# Relay_Mux_Sheet1.net
KiCad netlist of a schematic drawn in Altium Designer
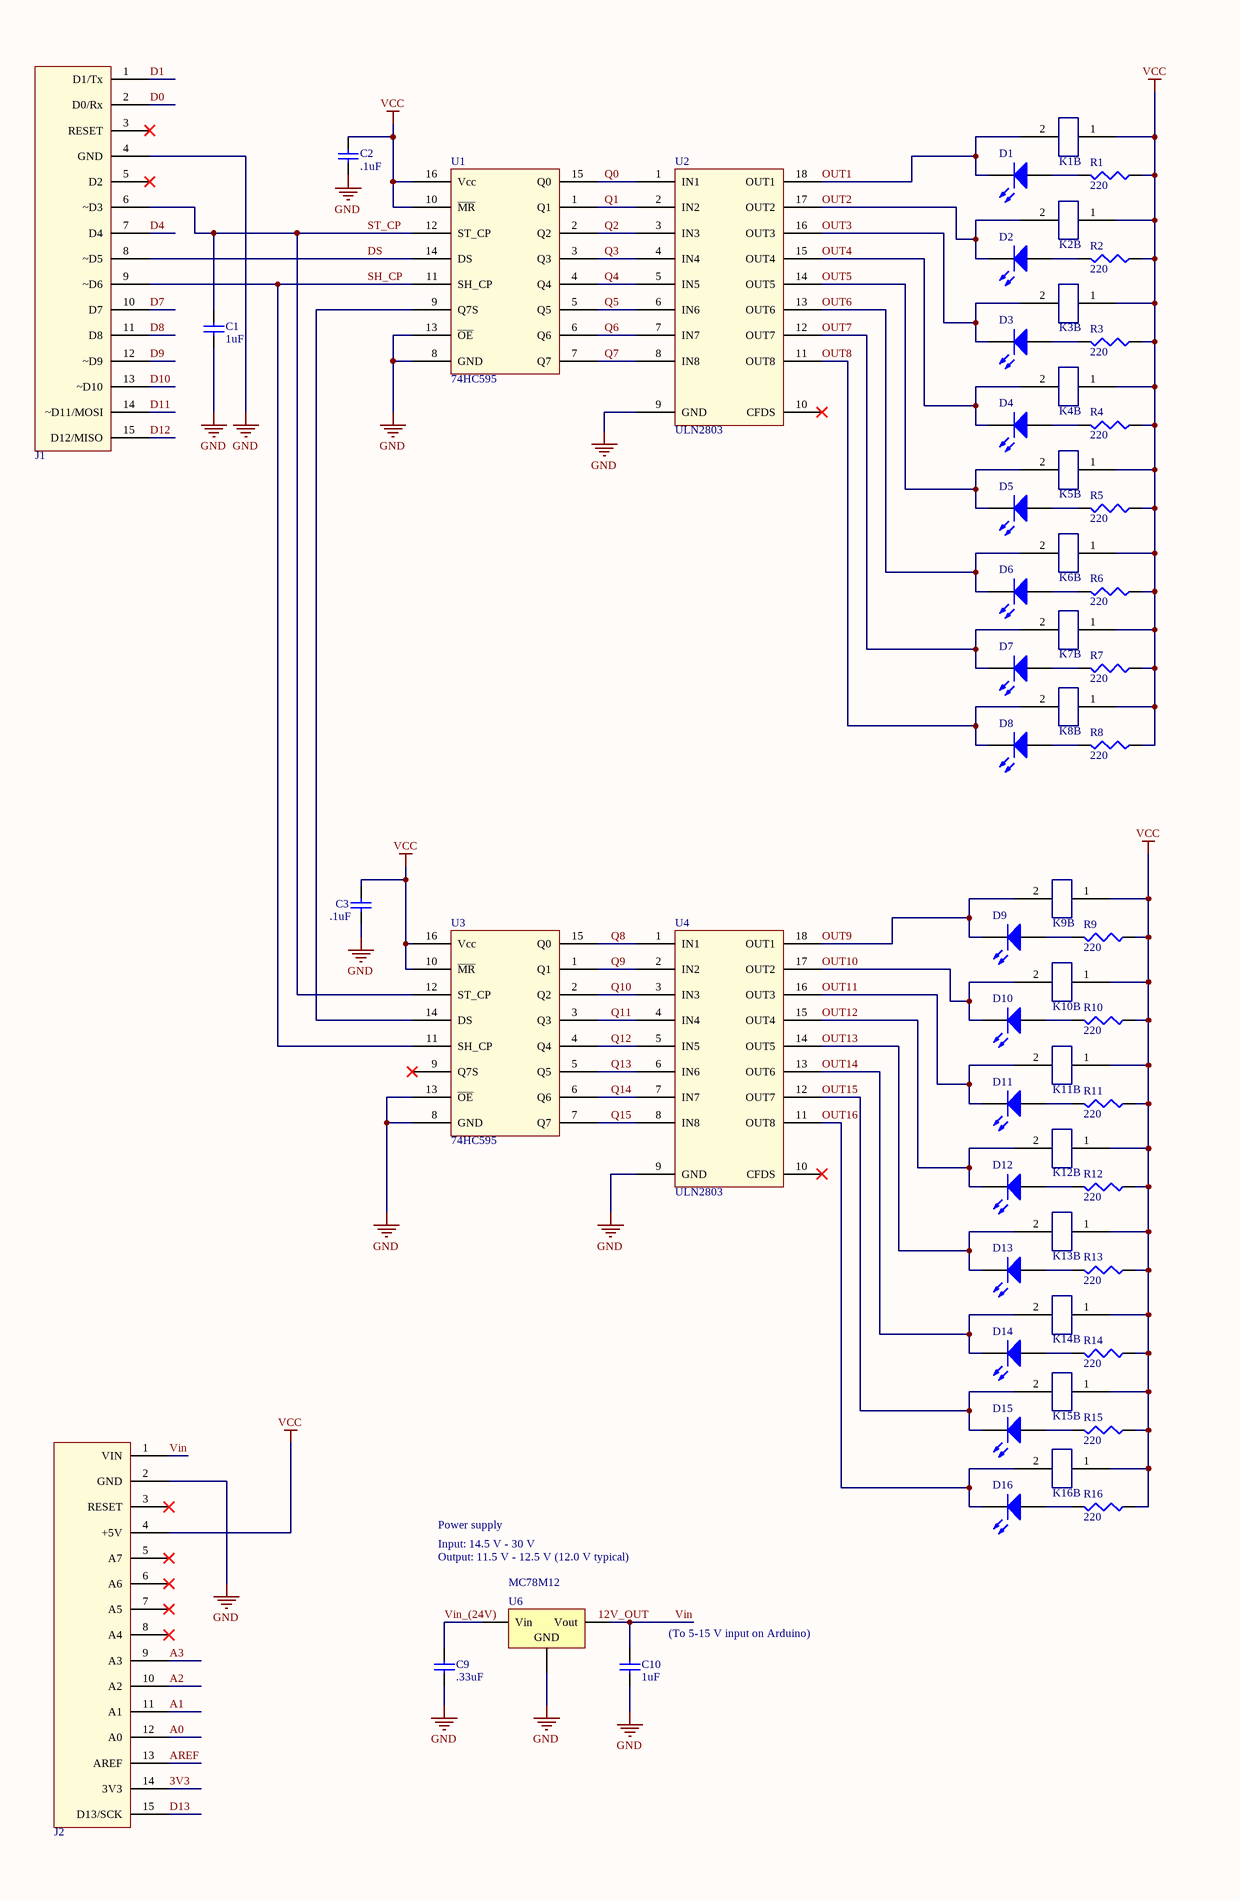
[diagram p0: Relay_Mux_Sheet1.SchDoc, left]
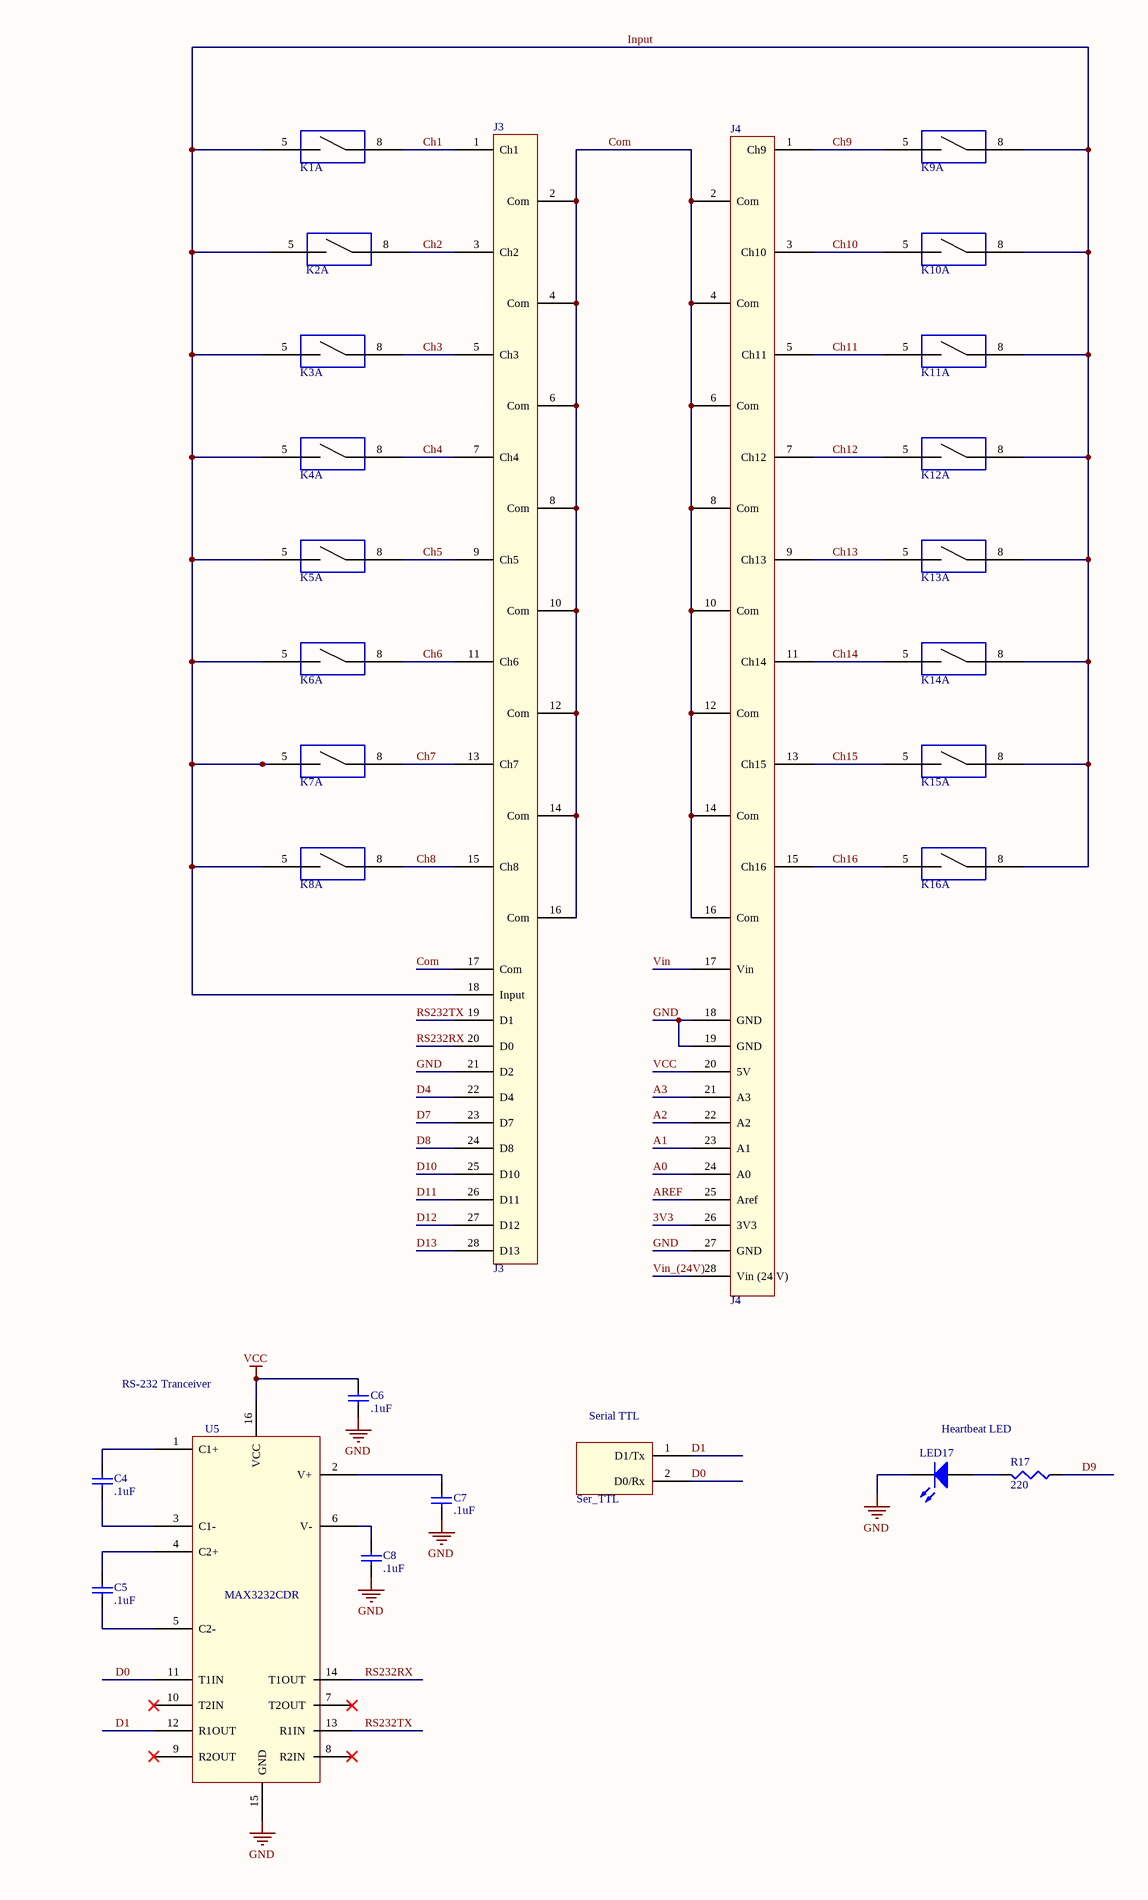
[diagram p1: Relay_Mux_Sheet1.SchDoc, right]

(export (version "E")
  (design (tool "Eeschema 10.0.6"))
  (components
    (comp (ref "C1")
      (value "1uF")
      (footprint "0603_Capacitor")
      (description "Capacitor")
      (fields (field (name "Comment") "Cap") (field (name "PUBLISHER") "Altium Limited"))
      (libsource (lib "Miscellaneous Devices") (part "Cap"))
    )
    (comp (ref "C2")
      (value ".1uF")
      (footprint "0603_Capacitor")
      (description "Capacitor")
      (fields (field (name "Comment") "Cap") (field (name "PUBLISHER") "Altium Limited"))
      (libsource (lib "Miscellaneous Devices") (part "Cap"))
    )
    (comp (ref "C3")
      (value ".1uF")
      (footprint "0603_Capacitor")
      (description "Capacitor")
      (fields (field (name "Comment") "Cap") (field (name "PUBLISHER") "Altium Limited"))
      (libsource (lib "Miscellaneous Devices") (part "Cap"))
    )
    (comp (ref "C4")
      (value ".1uF")
      (footprint "0603_Capacitor")
      (description "Capacitor")
      (fields (field (name "Comment") "Cap") (field (name "PUBLISHER") "Altium Limited"))
      (libsource (lib "Miscellaneous Devices") (part "Cap"))
    )
    (comp (ref "C5")
      (value ".1uF")
      (footprint "0603_Capacitor")
      (description "Capacitor")
      (fields (field (name "Comment") "Cap") (field (name "PUBLISHER") "Altium Limited"))
      (libsource (lib "Miscellaneous Devices") (part "Cap"))
    )
    (comp (ref "C6")
      (value ".1uF")
      (footprint "0603_Capacitor")
      (description "Capacitor")
      (fields (field (name "Comment") "Cap") (field (name "PUBLISHER") "Altium Limited"))
      (libsource (lib "Miscellaneous Devices") (part "Cap"))
    )
    (comp (ref "C7")
      (value ".1uF")
      (footprint "0603_Capacitor")
      (description "Capacitor")
      (fields (field (name "Comment") "Cap") (field (name "PUBLISHER") "Altium Limited"))
      (libsource (lib "Miscellaneous Devices") (part "Cap"))
    )
    (comp (ref "C8")
      (value ".1uF")
      (footprint "0603_Capacitor")
      (description "Capacitor")
      (fields (field (name "Comment") "Cap") (field (name "PUBLISHER") "Altium Limited"))
      (libsource (lib "Miscellaneous Devices") (part "Cap"))
    )
    (comp (ref "C9")
      (value ".33uF")
      (footprint "0603_Capacitor")
      (description "Capacitor")
      (fields (field (name "Comment") "Cap") (field (name "PUBLISHER") "Altium Limited"))
      (libsource (lib "Miscellaneous Devices") (part "Cap"))
    )
    (comp (ref "C10")
      (value "1uF")
      (footprint "0805_cap_CAPC3013X10N")
      (description "Capacitor")
      (fields (field (name "Comment") "Cap") (field (name "PUBLISHER") "Altium Limited"))
      (libsource (lib "Miscellaneous Devices") (part "Cap"))
    )
    (comp (ref "D1")
      (value "LED3")
      (footprint "LITE_ON_LED")
      (description "Typical BLUE SiC LED")
      (fields (field (name "PUBLISHER") "Altium Limited"))
      (libsource (lib "Miscellaneous Devices") (part "LED3"))
    )
    (comp (ref "D2")
      (value "LED3")
      (footprint "LITE_ON_LED")
      (description "Typical BLUE SiC LED")
      (fields (field (name "PUBLISHER") "Altium Limited"))
      (libsource (lib "Miscellaneous Devices") (part "LED3"))
    )
    (comp (ref "D3")
      (value "LED3")
      (footprint "LITE_ON_LED")
      (description "Typical BLUE SiC LED")
      (fields (field (name "PUBLISHER") "Altium Limited"))
      (libsource (lib "Miscellaneous Devices") (part "LED3"))
    )
    (comp (ref "D4")
      (value "LED3")
      (footprint "LITE_ON_LED")
      (description "Typical BLUE SiC LED")
      (fields (field (name "PUBLISHER") "Altium Limited"))
      (libsource (lib "Miscellaneous Devices") (part "LED3"))
    )
    (comp (ref "D5")
      (value "LED3")
      (footprint "LITE_ON_LED")
      (description "Typical BLUE SiC LED")
      (fields (field (name "PUBLISHER") "Altium Limited"))
      (libsource (lib "Miscellaneous Devices") (part "LED3"))
    )
    (comp (ref "D6")
      (value "LED3")
      (footprint "LITE_ON_LED")
      (description "Typical BLUE SiC LED")
      (fields (field (name "PUBLISHER") "Altium Limited"))
      (libsource (lib "Miscellaneous Devices") (part "LED3"))
    )
    (comp (ref "D7")
      (value "LED3")
      (footprint "LITE_ON_LED")
      (description "Typical BLUE SiC LED")
      (fields (field (name "PUBLISHER") "Altium Limited"))
      (libsource (lib "Miscellaneous Devices") (part "LED3"))
    )
    (comp (ref "D8")
      (value "LED3")
      (footprint "LITE_ON_LED")
      (description "Typical BLUE SiC LED")
      (fields (field (name "PUBLISHER") "Altium Limited"))
      (libsource (lib "Miscellaneous Devices") (part "LED3"))
    )
    (comp (ref "D9")
      (value "LED3")
      (footprint "LITE_ON_LED")
      (description "Typical BLUE SiC LED")
      (fields (field (name "PUBLISHER") "Altium Limited"))
      (libsource (lib "Miscellaneous Devices") (part "LED3"))
    )
    (comp (ref "D10")
      (value "LED3")
      (footprint "LITE_ON_LED")
      (description "Typical BLUE SiC LED")
      (fields (field (name "PUBLISHER") "Altium Limited"))
      (libsource (lib "Miscellaneous Devices") (part "LED3"))
    )
    (comp (ref "D11")
      (value "LED11")
      (footprint "LITE_ON_LED")
      (description "Typical BLUE SiC LED")
      (fields (field (name "PUBLISHER") "Altium Limited"))
      (libsource (lib "Miscellaneous Devices") (part "LED3"))
    )
    (comp (ref "D12")
      (value "LED3")
      (footprint "LITE_ON_LED")
      (description "Typical BLUE SiC LED")
      (fields (field (name "PUBLISHER") "Altium Limited"))
      (libsource (lib "Miscellaneous Devices") (part "LED3"))
    )
    (comp (ref "D13")
      (value "LED3")
      (footprint "LITE_ON_LED")
      (description "Typical BLUE SiC LED")
      (fields (field (name "PUBLISHER") "Altium Limited"))
      (libsource (lib "Miscellaneous Devices") (part "LED3"))
    )
    (comp (ref "D14")
      (value "LED3")
      (footprint "LITE_ON_LED")
      (description "Typical BLUE SiC LED")
      (fields (field (name "PUBLISHER") "Altium Limited"))
      (libsource (lib "Miscellaneous Devices") (part "LED3"))
    )
    (comp (ref "D15")
      (value "LED3")
      (footprint "LITE_ON_LED")
      (description "Typical BLUE SiC LED")
      (fields (field (name "PUBLISHER") "Altium Limited"))
      (libsource (lib "Miscellaneous Devices") (part "LED3"))
    )
    (comp (ref "D16")
      (value "LED3")
      (footprint "LITE_ON_LED")
      (description "Typical BLUE SiC LED")
      (fields (field (name "PUBLISHER") "Altium Limited"))
      (libsource (lib "Miscellaneous Devices") (part "LED3"))
    )
    (comp (ref "J1")
      (value "J1_Nano")
      (footprint "J1, J2 - Arduino Nano")
      (description "J1 on Arduino Nano")
      (libsource (lib "Relay_Mux") (part "J1"))
    )
    (comp (ref "J2")
      (value "J2_Nano")
      (footprint "J1, J2 - Arduino Nano")
      (description "J2 on Arduino Nano")
      (libsource (lib "Relay_Mux") (part "J2"))
    )
    (comp (ref "J3")
      (value "J3")
      (footprint "Term_Block_Amphenol_20020327")
      (libsource (lib "Relay_Mux") (part "J3"))
    )
    (comp (ref "J4")
      (value "J4")
      (footprint "Term_Block_Amphenol_20020327")
      (libsource (lib "Relay_Mux") (part "J4"))
    )
    (comp (ref "K1")
      (value "K*")
      (footprint "Relay_G6DN-1A DC5")
      (description "Relay, SPST, 5V")
      (libsource (lib "") (part "Relay_G6DN-1A DC5_1"))
    )
    (comp (ref "K2")
      (value "K*")
      (footprint "Relay_G6DN-1A DC5")
      (description "Relay, SPST, 5V")
      (libsource (lib "Relay_Mux") (part "Relay_G6DN-1A DC5"))
    )
    (comp (ref "K3")
      (value "K*")
      (footprint "Relay_G6DN-1A DC5")
      (description "Relay, SPST, 5V")
      (libsource (lib "") (part "Relay_G6DN-1A DC5_1"))
    )
    (comp (ref "K4")
      (value "K*")
      (footprint "Relay_G6DN-1A DC5")
      (description "Relay, SPST, 5V")
      (libsource (lib "") (part "Relay_G6DN-1A DC5_1"))
    )
    (comp (ref "K5")
      (value "K*")
      (footprint "Relay_G6DN-1A DC5")
      (description "Relay, SPST, 5V")
      (libsource (lib "Relay_Mux") (part "Relay_G6DN-1A DC5"))
    )
    (comp (ref "K6")
      (value "K*")
      (footprint "Relay_G6DN-1A DC5")
      (description "Relay, SPST, 5V")
      (libsource (lib "Relay_Mux") (part "Relay_G6DN-1A DC5"))
    )
    (comp (ref "K7")
      (value "K*")
      (footprint "Relay_G6DN-1A DC5")
      (description "Relay, SPST, 5V")
      (libsource (lib "") (part "Relay_G6DN-1A DC5_1"))
    )
    (comp (ref "K8")
      (value "K*")
      (footprint "Relay_G6DN-1A DC5")
      (description "Relay, SPST, 5V")
      (libsource (lib "Relay_Mux") (part "Relay_G6DN-1A DC5"))
    )
    (comp (ref "K9")
      (value "K*")
      (footprint "Relay_G6DN-1A DC5")
      (description "Relay, SPST, 5V")
      (libsource (lib "Relay_Mux") (part "Relay_G6DN-1A DC5"))
    )
    (comp (ref "K10")
      (value "K*")
      (footprint "Relay_G6DN-1A DC5")
      (description "Relay, SPST, 5V")
      (libsource (lib "") (part "Relay_G6DN-1A DC5_1"))
    )
    (comp (ref "K11")
      (value "K*")
      (footprint "Relay_G6DN-1A DC5")
      (description "Relay, SPST, 5V")
      (libsource (lib "Relay_Mux") (part "Relay_G6DN-1A DC5"))
    )
    (comp (ref "K12")
      (value "K*")
      (footprint "Relay_G6DN-1A DC5")
      (description "Relay, SPST, 5V")
      (libsource (lib "") (part "Relay_G6DN-1A DC5_1"))
    )
    (comp (ref "K13")
      (value "K*")
      (footprint "Relay_G6DN-1A DC5")
      (description "Relay, SPST, 5V")
      (libsource (lib "Relay_Mux") (part "Relay_G6DN-1A DC5"))
    )
    (comp (ref "K14")
      (value "K*")
      (footprint "Relay_G6DN-1A DC5")
      (description "Relay, SPST, 5V")
      (libsource (lib "Relay_Mux") (part "Relay_G6DN-1A DC5"))
    )
    (comp (ref "K15")
      (value "K*")
      (footprint "Relay_G6DN-1A DC5")
      (description "Relay, SPST, 5V")
      (libsource (lib "") (part "Relay_G6DN-1A DC5_1"))
    )
    (comp (ref "K16")
      (value "K*")
      (footprint "Relay_G6DN-1A DC5")
      (description "Relay, SPST, 5V")
      (libsource (lib "Relay_Mux") (part "Relay_G6DN-1A DC5"))
    )
    (comp (ref "LED17")
      (value "LED3")
      (footprint "LITE_ON_LED")
      (description "Typical BLUE SiC LED")
      (fields (field (name "PUBLISHER") "Altium Limited"))
      (libsource (lib "Miscellaneous Devices") (part "LED3"))
    )
    (comp (ref "R1")
      (value "220")
      (footprint "0603_Resistor")
      (description "Resistor")
      (fields (field (name "Comment") "Res3") (field (name "PUBLISHER") "Altium Limited"))
      (libsource (lib "Miscellaneous Devices") (part "Res3"))
    )
    (comp (ref "R2")
      (value "220")
      (footprint "0603_Resistor")
      (description "Resistor")
      (fields (field (name "Comment") "Res3") (field (name "PUBLISHER") "Altium Limited"))
      (libsource (lib "Miscellaneous Devices") (part "Res3"))
    )
    (comp (ref "R3")
      (value "220")
      (footprint "0603_Resistor")
      (description "Resistor")
      (fields (field (name "Comment") "Res3") (field (name "PUBLISHER") "Altium Limited"))
      (libsource (lib "Miscellaneous Devices") (part "Res3"))
    )
    (comp (ref "R4")
      (value "220")
      (footprint "0603_Resistor")
      (description "Resistor")
      (fields (field (name "Comment") "Res3") (field (name "PUBLISHER") "Altium Limited"))
      (libsource (lib "Miscellaneous Devices") (part "Res3"))
    )
    (comp (ref "R5")
      (value "220")
      (footprint "0603_Resistor")
      (description "Resistor")
      (fields (field (name "Comment") "Res3") (field (name "PUBLISHER") "Altium Limited"))
      (libsource (lib "Miscellaneous Devices") (part "Res3"))
    )
    (comp (ref "R6")
      (value "220")
      (footprint "0603_Resistor")
      (description "Resistor")
      (fields (field (name "Comment") "Res3") (field (name "PUBLISHER") "Altium Limited"))
      (libsource (lib "Miscellaneous Devices") (part "Res3"))
    )
    (comp (ref "R7")
      (value "220")
      (footprint "0603_Resistor")
      (description "Resistor")
      (fields (field (name "Comment") "Res3") (field (name "PUBLISHER") "Altium Limited"))
      (libsource (lib "Miscellaneous Devices") (part "Res3"))
    )
    (comp (ref "R8")
      (value "220")
      (footprint "0603_Resistor")
      (description "Resistor")
      (fields (field (name "Comment") "Res3") (field (name "PUBLISHER") "Altium Limited"))
      (libsource (lib "Miscellaneous Devices") (part "Res3"))
    )
    (comp (ref "R9")
      (value "220")
      (footprint "0603_Resistor")
      (description "Resistor")
      (fields (field (name "Comment") "Res3") (field (name "PUBLISHER") "Altium Limited"))
      (libsource (lib "Miscellaneous Devices") (part "Res3"))
    )
    (comp (ref "R10")
      (value "220")
      (footprint "0603_Resistor")
      (description "Resistor")
      (fields (field (name "Comment") "Res3") (field (name "PUBLISHER") "Altium Limited"))
      (libsource (lib "Miscellaneous Devices") (part "Res3"))
    )
    (comp (ref "R11")
      (value "220")
      (footprint "0603_Resistor")
      (description "Resistor")
      (fields (field (name "Comment") "Res3") (field (name "PUBLISHER") "Altium Limited"))
      (libsource (lib "Miscellaneous Devices") (part "Res3"))
    )
    (comp (ref "R12")
      (value "220")
      (footprint "0603_Resistor")
      (description "Resistor")
      (fields (field (name "Comment") "Res3") (field (name "PUBLISHER") "Altium Limited"))
      (libsource (lib "Miscellaneous Devices") (part "Res3"))
    )
    (comp (ref "R13")
      (value "220")
      (footprint "0603_Resistor")
      (description "Resistor")
      (fields (field (name "Comment") "Res3") (field (name "PUBLISHER") "Altium Limited"))
      (libsource (lib "Miscellaneous Devices") (part "Res3"))
    )
    (comp (ref "R14")
      (value "220")
      (footprint "0603_Resistor")
      (description "Resistor")
      (fields (field (name "Comment") "Res3") (field (name "PUBLISHER") "Altium Limited"))
      (libsource (lib "Miscellaneous Devices") (part "Res3"))
    )
    (comp (ref "R15")
      (value "220")
      (footprint "0603_Resistor")
      (description "Resistor")
      (fields (field (name "Comment") "Res3") (field (name "PUBLISHER") "Altium Limited"))
      (libsource (lib "Miscellaneous Devices") (part "Res3"))
    )
    (comp (ref "R16")
      (value "220")
      (footprint "0603_Resistor")
      (description "Resistor")
      (fields (field (name "Comment") "Res3") (field (name "PUBLISHER") "Altium Limited"))
      (libsource (lib "Miscellaneous Devices") (part "Res3"))
    )
    (comp (ref "R17")
      (value "220")
      (footprint "0603_Resistor")
      (description "Resistor")
      (fields (field (name "Comment") "Res3") (field (name "PUBLISHER") "Altium Limited"))
      (libsource (lib "Miscellaneous Devices") (part "Res3"))
    )
    (comp (ref "Ser_TTL")
      (value "Ser_TTL")
      (footprint "Ser_TTL")
      (libsource (lib "Relay_Mux") (part "Ser_TTL"))
    )
    (comp (ref "U1")
      (value "74HC595")
      (footprint "16Pin_SOIC127P1030X265-16N")
      (libsource (lib "Relay_Mux") (part "74HC595"))
    )
    (comp (ref "U2")
      (value "ULN2803")
      (footprint "18Pin_SOIC127P1030X265-18N")
      (libsource (lib "Relay_Mux") (part "ULN2803"))
    )
    (comp (ref "U3")
      (value "74HC595")
      (footprint "16Pin_SOIC127P1030X265-16N")
      (libsource (lib "Relay_Mux") (part "74HC595"))
    )
    (comp (ref "U4")
      (value "ULN2803")
      (footprint "18Pin_SOIC127P1030X265-18N")
      (libsource (lib "Relay_Mux") (part "ULN2803"))
    )
    (comp (ref "U5")
      (value "MAX3232")
      (footprint "16 pin SOIC - MAX3232 - SOIC127P600X175-16N")
      (libsource (lib "Relay_Mux") (part "MAX3232"))
    )
    (comp (ref "U6")
      (value "MC78M12")
      (footprint "MC78M12 footprint - linear regulator - DPAK228P992X238-3N")
      (description "Voltage Regulator")
      (fields (field (name "PUBLISHER") "Altium Limited"))
      (libsource (lib "Miscellaneous Devices") (part "Volt Reg"))
    )
  )
  (nets
    (net (code "1") (name "/3V3") (class "Default")
      (node (ref "J2") (pin "14") (pinfunction "3V3_14") (pintype "passive"))
      (node (ref "J4") (pin "26") (pinfunction "3V3_26") (pintype "passive"))
    )
    (net (code "3") (name "/A0") (class "Default")
      (node (ref "J2") (pin "12") (pinfunction "A0_12") (pintype "passive"))
      (node (ref "J4") (pin "24") (pinfunction "A0_24") (pintype "passive"))
    )
    (net (code "4") (name "/A1") (class "Default")
      (node (ref "J2") (pin "11") (pinfunction "A1_11") (pintype "passive"))
      (node (ref "J4") (pin "23") (pinfunction "A1_23") (pintype "passive"))
    )
    (net (code "5") (name "/A2") (class "Default")
      (node (ref "J2") (pin "10") (pinfunction "A2_10") (pintype "passive"))
      (node (ref "J4") (pin "22") (pinfunction "A2_22") (pintype "passive"))
    )
    (net (code "6") (name "/A3") (class "Default")
      (node (ref "J2") (pin "9") (pinfunction "A3_9") (pintype "passive"))
      (node (ref "J4") (pin "21") (pinfunction "A3_21") (pintype "passive"))
    )
    (net (code "7") (name "/AREF") (class "Default")
      (node (ref "J2") (pin "13") (pinfunction "AREF_13") (pintype "passive"))
      (node (ref "J4") (pin "25") (pinfunction "Aref_25") (pintype "passive"))
    )
    (net (code "8") (name "/Ch1") (class "Default")
      (node (ref "J3") (pin "1") (pinfunction "Ch1_1") (pintype "passive"))
      (node (ref "K1") (pin "8") (pinfunction "8_8") (pintype "passive"))
    )
    (net (code "9") (name "/Ch2") (class "Default")
      (node (ref "J3") (pin "3") (pinfunction "Ch2_3") (pintype "passive"))
      (node (ref "K2") (pin "8") (pinfunction "8_8") (pintype "passive"))
    )
    (net (code "10") (name "/Ch3") (class "Default")
      (node (ref "J3") (pin "5") (pinfunction "Ch3_5") (pintype "passive"))
      (node (ref "K3") (pin "8") (pinfunction "8_8") (pintype "passive"))
    )
    (net (code "11") (name "/Ch4") (class "Default")
      (node (ref "J3") (pin "7") (pinfunction "Ch4_7") (pintype "passive"))
      (node (ref "K4") (pin "8") (pinfunction "8_8") (pintype "passive"))
    )
    (net (code "12") (name "/Ch5") (class "Default")
      (node (ref "J3") (pin "9") (pinfunction "Ch5_9") (pintype "passive"))
      (node (ref "K5") (pin "8") (pinfunction "8_8") (pintype "passive"))
    )
    (net (code "13") (name "/Ch6") (class "Default")
      (node (ref "J3") (pin "11") (pinfunction "Ch6_11") (pintype "passive"))
      (node (ref "K6") (pin "8") (pinfunction "8_8") (pintype "passive"))
    )
    (net (code "14") (name "/Ch7") (class "Default")
      (node (ref "J3") (pin "13") (pinfunction "Ch7_13") (pintype "passive"))
      (node (ref "K7") (pin "8") (pinfunction "8_8") (pintype "passive"))
    )
    (net (code "15") (name "/Ch8") (class "Default")
      (node (ref "J3") (pin "15") (pinfunction "Ch8_15") (pintype "passive"))
      (node (ref "K8") (pin "8") (pinfunction "8_8") (pintype "passive"))
    )
    (net (code "16") (name "/Ch9") (class "Default")
      (node (ref "J4") (pin "1") (pinfunction "Ch9_1") (pintype "passive"))
      (node (ref "K9") (pin "5") (pinfunction "5_5") (pintype "passive"))
    )
    (net (code "17") (name "/Ch10") (class "Default")
      (node (ref "J4") (pin "3") (pinfunction "Ch10_3") (pintype "passive"))
      (node (ref "K10") (pin "5") (pinfunction "5_5") (pintype "passive"))
    )
    (net (code "18") (name "/Ch11") (class "Default")
      (node (ref "J4") (pin "5") (pinfunction "Ch11_5") (pintype "passive"))
      (node (ref "K11") (pin "5") (pinfunction "5_5") (pintype "passive"))
    )
    (net (code "19") (name "/Ch12") (class "Default")
      (node (ref "J4") (pin "7") (pinfunction "Ch12_7") (pintype "passive"))
      (node (ref "K12") (pin "5") (pinfunction "5_5") (pintype "passive"))
    )
    (net (code "20") (name "/Ch13") (class "Default")
      (node (ref "J4") (pin "9") (pinfunction "Ch13_9") (pintype "passive"))
      (node (ref "K13") (pin "5") (pinfunction "5_5") (pintype "passive"))
    )
    (net (code "21") (name "/Ch14") (class "Default")
      (node (ref "J4") (pin "11") (pinfunction "Ch14_11") (pintype "passive"))
      (node (ref "K14") (pin "5") (pinfunction "5_5") (pintype "passive"))
    )
    (net (code "22") (name "/Ch15") (class "Default")
      (node (ref "J4") (pin "13") (pinfunction "Ch15_13") (pintype "passive"))
      (node (ref "K15") (pin "5") (pinfunction "5_5") (pintype "passive"))
    )
    (net (code "23") (name "/Ch16") (class "Default")
      (node (ref "J4") (pin "15") (pinfunction "Ch16_15") (pintype "passive"))
      (node (ref "K16") (pin "5") (pinfunction "5_5") (pintype "passive"))
    )
    (net (code "24") (name "/Com") (class "Default")
      (node (ref "J3") (pin "10") (pinfunction "Com_10") (pintype "passive"))
      (node (ref "J3") (pin "12") (pinfunction "Com_12") (pintype "passive"))
      (node (ref "J3") (pin "14") (pinfunction "Com_14") (pintype "passive"))
      (node (ref "J3") (pin "16") (pinfunction "Com_16") (pintype "passive"))
      (node (ref "J3") (pin "17") (pinfunction "Com_17") (pintype "passive"))
      (node (ref "J3") (pin "2") (pinfunction "Com_2") (pintype "passive"))
      (node (ref "J3") (pin "4") (pinfunction "Com_4") (pintype "passive"))
      (node (ref "J3") (pin "6") (pinfunction "Com_6") (pintype "passive"))
      (node (ref "J3") (pin "8") (pinfunction "Com_8") (pintype "passive"))
      (node (ref "J4") (pin "10") (pinfunction "Com_10") (pintype "passive"))
      (node (ref "J4") (pin "12") (pinfunction "Com_12") (pintype "passive"))
      (node (ref "J4") (pin "14") (pinfunction "Com_14") (pintype "passive"))
      (node (ref "J4") (pin "16") (pinfunction "Com_16") (pintype "passive"))
      (node (ref "J4") (pin "2") (pinfunction "Com_2") (pintype "passive"))
      (node (ref "J4") (pin "4") (pinfunction "Com_4") (pintype "passive"))
      (node (ref "J4") (pin "6") (pinfunction "Com_6") (pintype "passive"))
      (node (ref "J4") (pin "8") (pinfunction "Com_8") (pintype "passive"))
    )
    (net (code "25") (name "/D0") (class "Default")
      (node (ref "J1") (pin "2") (pinfunction "D0/Rx_2") (pintype "passive"))
      (node (ref "Ser_TTL") (pin "2") (pinfunction "D0/Rx_2") (pintype "passive"))
      (node (ref "U5") (pin "11") (pinfunction "T1IN_11") (pintype "passive"))
    )
    (net (code "26") (name "/D1") (class "Default")
      (node (ref "J1") (pin "1") (pinfunction "D1/Tx_1") (pintype "passive"))
      (node (ref "Ser_TTL") (pin "1") (pinfunction "D1/Tx_1") (pintype "passive"))
      (node (ref "U5") (pin "12") (pinfunction "R1OUT_12") (pintype "passive"))
    )
    (net (code "27") (name "/D4") (class "Default")
      (node (ref "J1") (pin "7") (pinfunction "D4_7") (pintype "passive"))
      (node (ref "J3") (pin "22") (pinfunction "D4_22") (pintype "passive"))
    )
    (net (code "28") (name "/D7") (class "Default")
      (node (ref "J1") (pin "10") (pinfunction "D7_10") (pintype "passive"))
      (node (ref "J3") (pin "23") (pinfunction "D7_23") (pintype "passive"))
    )
    (net (code "29") (name "/D8") (class "Default")
      (node (ref "J1") (pin "11") (pinfunction "D8_11") (pintype "passive"))
      (node (ref "J3") (pin "24") (pinfunction "D8_24") (pintype "passive"))
    )
    (net (code "30") (name "/D9") (class "Default")
      (node (ref "J1") (pin "12") (pinfunction "~D9_12") (pintype "passive"))
      (node (ref "R17") (pin "1") (pinfunction "1_1") (pintype "passive"))
    )
    (net (code "31") (name "/D10") (class "Default")
      (node (ref "J1") (pin "13") (pinfunction "~D10_13") (pintype "passive"))
      (node (ref "J3") (pin "25") (pinfunction "D10_25") (pintype "passive"))
    )
    (net (code "32") (name "/D11") (class "Default")
      (node (ref "J1") (pin "14") (pinfunction "~D11/MOSI_14") (pintype "passive"))
      (node (ref "J3") (pin "26") (pinfunction "D11_26") (pintype "passive"))
    )
    (net (code "33") (name "/D12") (class "Default")
      (node (ref "J1") (pin "15") (pinfunction "D12/MISO_15") (pintype "passive"))
      (node (ref "J3") (pin "27") (pinfunction "D12_27") (pintype "passive"))
    )
    (net (code "34") (name "/D13") (class "Default")
      (node (ref "J2") (pin "15") (pinfunction "D13/SCK_15") (pintype "passive"))
      (node (ref "J3") (pin "28") (pinfunction "D13_28") (pintype "passive"))
    )
    (net (code "35") (name "/DS") (class "Default")
      (node (ref "J1") (pin "8") (pinfunction "~D5_8") (pintype "passive"))
      (node (ref "U1") (pin "14") (pinfunction "DS_14") (pintype "passive"))
    )
    (net (code "36") (name "/Input") (class "Default")
      (node (ref "J3") (pin "18") (pinfunction "Input_18") (pintype "passive"))
      (node (ref "K1") (pin "5") (pinfunction "5_5") (pintype "passive"))
      (node (ref "K10") (pin "8") (pinfunction "8_8") (pintype "passive"))
      (node (ref "K11") (pin "8") (pinfunction "8_8") (pintype "passive"))
      (node (ref "K12") (pin "8") (pinfunction "8_8") (pintype "passive"))
      (node (ref "K13") (pin "8") (pinfunction "8_8") (pintype "passive"))
      (node (ref "K14") (pin "8") (pinfunction "8_8") (pintype "passive"))
      (node (ref "K15") (pin "8") (pinfunction "8_8") (pintype "passive"))
      (node (ref "K16") (pin "8") (pinfunction "8_8") (pintype "passive"))
      (node (ref "K2") (pin "5") (pinfunction "5_5") (pintype "passive"))
      (node (ref "K3") (pin "5") (pinfunction "5_5") (pintype "passive"))
      (node (ref "K4") (pin "5") (pinfunction "5_5") (pintype "passive"))
      (node (ref "K5") (pin "5") (pinfunction "5_5") (pintype "passive"))
      (node (ref "K6") (pin "5") (pinfunction "5_5") (pintype "passive"))
      (node (ref "K7") (pin "5") (pinfunction "5_5") (pintype "passive"))
      (node (ref "K8") (pin "5") (pinfunction "5_5") (pintype "passive"))
      (node (ref "K9") (pin "8") (pinfunction "8_8") (pintype "passive"))
    )
    (net (code "37") (name "/OUT1") (class "Default")
      (node (ref "D1") (pin "2") (pinfunction "K_2") (pintype "passive"))
      (node (ref "K1") (pin "2") (pinfunction "2_2") (pintype "passive"))
      (node (ref "U2") (pin "18") (pinfunction "OUT1_18") (pintype "passive"))
    )
    (net (code "38") (name "/OUT2") (class "Default")
      (node (ref "D2") (pin "2") (pinfunction "K_2") (pintype "passive"))
      (node (ref "K2") (pin "2") (pinfunction "2_2") (pintype "passive"))
      (node (ref "U2") (pin "17") (pinfunction "OUT2_17") (pintype "passive"))
    )
    (net (code "39") (name "/OUT3") (class "Default")
      (node (ref "D3") (pin "2") (pinfunction "K_2") (pintype "passive"))
      (node (ref "K3") (pin "2") (pinfunction "2_2") (pintype "passive"))
      (node (ref "U2") (pin "16") (pinfunction "OUT3_16") (pintype "passive"))
    )
    (net (code "40") (name "/OUT4") (class "Default")
      (node (ref "D4") (pin "2") (pinfunction "K_2") (pintype "passive"))
      (node (ref "K4") (pin "2") (pinfunction "2_2") (pintype "passive"))
      (node (ref "U2") (pin "15") (pinfunction "OUT4_15") (pintype "passive"))
    )
    (net (code "41") (name "/OUT5") (class "Default")
      (node (ref "D5") (pin "2") (pinfunction "K_2") (pintype "passive"))
      (node (ref "K5") (pin "2") (pinfunction "2_2") (pintype "passive"))
      (node (ref "U2") (pin "14") (pinfunction "OUT5_14") (pintype "passive"))
    )
    (net (code "42") (name "/OUT6") (class "Default")
      (node (ref "D6") (pin "2") (pinfunction "K_2") (pintype "passive"))
      (node (ref "K6") (pin "2") (pinfunction "2_2") (pintype "passive"))
      (node (ref "U2") (pin "13") (pinfunction "OUT6_13") (pintype "passive"))
    )
    (net (code "43") (name "/OUT7") (class "Default")
      (node (ref "D7") (pin "2") (pinfunction "K_2") (pintype "passive"))
      (node (ref "K7") (pin "2") (pinfunction "2_2") (pintype "passive"))
      (node (ref "U2") (pin "12") (pinfunction "OUT7_12") (pintype "passive"))
    )
    (net (code "44") (name "/OUT8") (class "Default")
      (node (ref "D8") (pin "2") (pinfunction "K_2") (pintype "passive"))
      (node (ref "K8") (pin "2") (pinfunction "2_2") (pintype "passive"))
      (node (ref "U2") (pin "11") (pinfunction "OUT8_11") (pintype "passive"))
    )
    (net (code "45") (name "/OUT9") (class "Default")
      (node (ref "D9") (pin "2") (pinfunction "K_2") (pintype "passive"))
      (node (ref "K9") (pin "2") (pinfunction "2_2") (pintype "passive"))
      (node (ref "U4") (pin "18") (pinfunction "OUT1_18") (pintype "passive"))
    )
    (net (code "46") (name "/OUT10") (class "Default")
      (node (ref "D10") (pin "2") (pinfunction "K_2") (pintype "passive"))
      (node (ref "K10") (pin "2") (pinfunction "2_2") (pintype "passive"))
      (node (ref "U4") (pin "17") (pinfunction "OUT2_17") (pintype "passive"))
    )
    (net (code "47") (name "/OUT11") (class "Default")
      (node (ref "D11") (pin "2") (pinfunction "K_2") (pintype "passive"))
      (node (ref "K11") (pin "2") (pinfunction "2_2") (pintype "passive"))
      (node (ref "U4") (pin "16") (pinfunction "OUT3_16") (pintype "passive"))
    )
    (net (code "48") (name "/OUT12") (class "Default")
      (node (ref "D12") (pin "2") (pinfunction "K_2") (pintype "passive"))
      (node (ref "K12") (pin "2") (pinfunction "2_2") (pintype "passive"))
      (node (ref "U4") (pin "15") (pinfunction "OUT4_15") (pintype "passive"))
    )
    (net (code "49") (name "/OUT13") (class "Default")
      (node (ref "D13") (pin "2") (pinfunction "K_2") (pintype "passive"))
      (node (ref "K13") (pin "2") (pinfunction "2_2") (pintype "passive"))
      (node (ref "U4") (pin "14") (pinfunction "OUT5_14") (pintype "passive"))
    )
    (net (code "50") (name "/OUT14") (class "Default")
      (node (ref "D14") (pin "2") (pinfunction "K_2") (pintype "passive"))
      (node (ref "K14") (pin "2") (pinfunction "2_2") (pintype "passive"))
      (node (ref "U4") (pin "13") (pinfunction "OUT6_13") (pintype "passive"))
    )
    (net (code "51") (name "/OUT15") (class "Default")
      (node (ref "D15") (pin "2") (pinfunction "K_2") (pintype "passive"))
      (node (ref "K15") (pin "2") (pinfunction "2_2") (pintype "passive"))
      (node (ref "U4") (pin "12") (pinfunction "OUT7_12") (pintype "passive"))
    )
    (net (code "52") (name "/OUT16") (class "Default")
      (node (ref "D16") (pin "2") (pinfunction "K_2") (pintype "passive"))
      (node (ref "K16") (pin "2") (pinfunction "2_2") (pintype "passive"))
      (node (ref "U4") (pin "11") (pinfunction "OUT8_11") (pintype "passive"))
    )
    (net (code "53") (name "/Q0") (class "Default")
      (node (ref "U1") (pin "15") (pinfunction "Q0_15") (pintype "passive"))
      (node (ref "U2") (pin "1") (pinfunction "IN1_1") (pintype "passive"))
    )
    (net (code "54") (name "/Q1") (class "Default")
      (node (ref "U1") (pin "1") (pinfunction "Q1_1") (pintype "passive"))
      (node (ref "U2") (pin "2") (pinfunction "IN2_2") (pintype "passive"))
    )
    (net (code "55") (name "/Q2") (class "Default")
      (node (ref "U1") (pin "2") (pinfunction "Q2_2") (pintype "passive"))
      (node (ref "U2") (pin "3") (pinfunction "IN3_3") (pintype "passive"))
    )
    (net (code "56") (name "/Q3") (class "Default")
      (node (ref "U1") (pin "3") (pinfunction "Q3_3") (pintype "passive"))
      (node (ref "U2") (pin "4") (pinfunction "IN4_4") (pintype "passive"))
    )
    (net (code "57") (name "/Q4") (class "Default")
      (node (ref "U1") (pin "4") (pinfunction "Q4_4") (pintype "passive"))
      (node (ref "U2") (pin "5") (pinfunction "IN5_5") (pintype "passive"))
    )
    (net (code "58") (name "/Q5") (class "Default")
      (node (ref "U1") (pin "5") (pinfunction "Q5_5") (pintype "passive"))
      (node (ref "U2") (pin "6") (pinfunction "IN6_6") (pintype "passive"))
    )
    (net (code "59") (name "/Q6") (class "Default")
      (node (ref "U1") (pin "6") (pinfunction "Q6_6") (pintype "passive"))
      (node (ref "U2") (pin "7") (pinfunction "IN7_7") (pintype "passive"))
    )
    (net (code "60") (name "/Q7") (class "Default")
      (node (ref "U1") (pin "7") (pinfunction "Q7_7") (pintype "passive"))
      (node (ref "U2") (pin "8") (pinfunction "IN8_8") (pintype "passive"))
    )
    (net (code "61") (name "/Q8") (class "Default")
      (node (ref "U3") (pin "15") (pinfunction "Q0_15") (pintype "passive"))
      (node (ref "U4") (pin "1") (pinfunction "IN1_1") (pintype "passive"))
    )
    (net (code "62") (name "/Q9") (class "Default")
      (node (ref "U3") (pin "1") (pinfunction "Q1_1") (pintype "passive"))
      (node (ref "U4") (pin "2") (pinfunction "IN2_2") (pintype "passive"))
    )
    (net (code "63") (name "/Q10") (class "Default")
      (node (ref "U3") (pin "2") (pinfunction "Q2_2") (pintype "passive"))
      (node (ref "U4") (pin "3") (pinfunction "IN3_3") (pintype "passive"))
    )
    (net (code "64") (name "/Q11") (class "Default")
      (node (ref "U3") (pin "3") (pinfunction "Q3_3") (pintype "passive"))
      (node (ref "U4") (pin "4") (pinfunction "IN4_4") (pintype "passive"))
    )
    (net (code "65") (name "/Q12") (class "Default")
      (node (ref "U3") (pin "4") (pinfunction "Q4_4") (pintype "passive"))
      (node (ref "U4") (pin "5") (pinfunction "IN5_5") (pintype "passive"))
    )
    (net (code "66") (name "/Q13") (class "Default")
      (node (ref "U3") (pin "5") (pinfunction "Q5_5") (pintype "passive"))
      (node (ref "U4") (pin "6") (pinfunction "IN6_6") (pintype "passive"))
    )
    (net (code "67") (name "/Q14") (class "Default")
      (node (ref "U3") (pin "6") (pinfunction "Q6_6") (pintype "passive"))
      (node (ref "U4") (pin "7") (pinfunction "IN7_7") (pintype "passive"))
    )
    (net (code "68") (name "/Q15") (class "Default")
      (node (ref "U3") (pin "7") (pinfunction "Q7_7") (pintype "passive"))
      (node (ref "U4") (pin "8") (pinfunction "IN8_8") (pintype "passive"))
    )
    (net (code "69") (name "/RS232RX") (class "Default")
      (node (ref "J3") (pin "20") (pinfunction "D0_20") (pintype "passive"))
      (node (ref "U5") (pin "14") (pinfunction "T1OUT_14") (pintype "passive"))
    )
    (net (code "70") (name "/RS232TX") (class "Default")
      (node (ref "J3") (pin "19") (pinfunction "D1_19") (pintype "passive"))
      (node (ref "U5") (pin "13") (pinfunction "R1IN_13") (pintype "passive"))
    )
    (net (code "71") (name "/SH_CP") (class "Default")
      (node (ref "J1") (pin "9") (pinfunction "~D6_9") (pintype "passive"))
      (node (ref "U1") (pin "11") (pinfunction "SH_CP_11") (pintype "passive"))
      (node (ref "U3") (pin "11") (pinfunction "SH_CP_11") (pintype "passive"))
    )
    (net (code "72") (name "/ST_CP") (class "Default")
      (node (ref "C1") (pin "2") (pinfunction "2_2") (pintype "passive"))
      (node (ref "J1") (pin "6") (pinfunction "~D3_6") (pintype "passive"))
      (node (ref "U1") (pin "12") (pinfunction "ST_CP_12") (pintype "passive"))
      (node (ref "U3") (pin "12") (pinfunction "ST_CP_12") (pintype "passive"))
    )
    (net (code "73") (name "/Vin") (class "Default")
      (node (ref "C10") (pin "1") (pinfunction "1_1") (pintype "passive"))
      (node (ref "J2") (pin "1") (pinfunction "VIN_1") (pintype "passive"))
      (node (ref "J4") (pin "17") (pinfunction "Vin_17") (pintype "passive"))
      (node (ref "U6") (pin "3") (pinfunction "Vout_3") (pintype "passive"))
    )
    (net (code "74") (name "/Vin_(24V)") (class "Default")
      (node (ref "C9") (pin "1") (pinfunction "1_1") (pintype "passive"))
      (node (ref "J4") (pin "28") (pinfunction "Vin_(24_V)_28") (pintype "passive"))
      (node (ref "U6") (pin "1") (pinfunction "Vin_1") (pintype "passive"))
    )
    (net (code "75") (name "GND") (class "Default")
      (node (ref "C1") (pin "1") (pinfunction "1_1") (pintype "passive"))
      (node (ref "C10") (pin "2") (pinfunction "2_2") (pintype "passive"))
      (node (ref "C2") (pin "1") (pinfunction "1_1") (pintype "passive"))
      (node (ref "C3") (pin "1") (pinfunction "1_1") (pintype "passive"))
      (node (ref "C6") (pin "2") (pinfunction "2_2") (pintype "passive"))
      (node (ref "C7") (pin "2") (pinfunction "2_2") (pintype "passive"))
      (node (ref "C8") (pin "2") (pinfunction "2_2") (pintype "passive"))
      (node (ref "C9") (pin "2") (pinfunction "2_2") (pintype "passive"))
      (node (ref "J1") (pin "4") (pinfunction "GND_4") (pintype "passive"))
      (node (ref "J2") (pin "2") (pinfunction "GND_2") (pintype "passive"))
      (node (ref "J3") (pin "21") (pinfunction "D2_21") (pintype "passive"))
      (node (ref "J4") (pin "18") (pinfunction "GND_18") (pintype "passive"))
      (node (ref "J4") (pin "19") (pinfunction "GND_19") (pintype "passive"))
      (node (ref "J4") (pin "27") (pinfunction "GND_27") (pintype "passive"))
      (node (ref "LED17") (pin "2") (pinfunction "K_2") (pintype "passive"))
      (node (ref "U1") (pin "13") (pinfunction "~{OE}_13") (pintype "passive"))
      (node (ref "U1") (pin "8") (pinfunction "GND_8") (pintype "passive"))
      (node (ref "U2") (pin "9") (pinfunction "GND_9") (pintype "passive"))
      (node (ref "U3") (pin "13") (pinfunction "~{OE}_13") (pintype "passive"))
      (node (ref "U3") (pin "8") (pinfunction "GND_8") (pintype "passive"))
      (node (ref "U4") (pin "9") (pinfunction "GND_9") (pintype "passive"))
      (node (ref "U5") (pin "15") (pinfunction "GND_15") (pintype "passive"))
      (node (ref "U6") (pin "2") (pinfunction "GND_2") (pintype "passive"))
    )
    (net (code "76") (name "Net-(D1-A)") (class "Default")
      (node (ref "D1") (pin "1") (pinfunction "A_1") (pintype "passive"))
      (node (ref "R1") (pin "2") (pinfunction "2_2") (pintype "passive"))
    )
    (net (code "77") (name "Net-(D2-A)") (class "Default")
      (node (ref "D2") (pin "1") (pinfunction "A_1") (pintype "passive"))
      (node (ref "R2") (pin "2") (pinfunction "2_2") (pintype "passive"))
    )
    (net (code "78") (name "Net-(D3-A)") (class "Default")
      (node (ref "D3") (pin "1") (pinfunction "A_1") (pintype "passive"))
      (node (ref "R3") (pin "2") (pinfunction "2_2") (pintype "passive"))
    )
    (net (code "79") (name "Net-(D4-A)") (class "Default")
      (node (ref "D4") (pin "1") (pinfunction "A_1") (pintype "passive"))
      (node (ref "R4") (pin "2") (pinfunction "2_2") (pintype "passive"))
    )
    (net (code "80") (name "Net-(D5-A)") (class "Default")
      (node (ref "D5") (pin "1") (pinfunction "A_1") (pintype "passive"))
      (node (ref "R5") (pin "2") (pinfunction "2_2") (pintype "passive"))
    )
    (net (code "81") (name "Net-(D6-A)") (class "Default")
      (node (ref "D6") (pin "1") (pinfunction "A_1") (pintype "passive"))
      (node (ref "R6") (pin "2") (pinfunction "2_2") (pintype "passive"))
    )
    (net (code "82") (name "Net-(D7-A)") (class "Default")
      (node (ref "D7") (pin "1") (pinfunction "A_1") (pintype "passive"))
      (node (ref "R7") (pin "2") (pinfunction "2_2") (pintype "passive"))
    )
    (net (code "83") (name "Net-(D8-A)") (class "Default")
      (node (ref "D8") (pin "1") (pinfunction "A_1") (pintype "passive"))
      (node (ref "R8") (pin "2") (pinfunction "2_2") (pintype "passive"))
    )
    (net (code "84") (name "Net-(D9-A)") (class "Default")
      (node (ref "D9") (pin "1") (pinfunction "A_1") (pintype "passive"))
      (node (ref "R9") (pin "2") (pinfunction "2_2") (pintype "passive"))
    )
    (net (code "85") (name "Net-(D10-A)") (class "Default")
      (node (ref "D10") (pin "1") (pinfunction "A_1") (pintype "passive"))
      (node (ref "R10") (pin "2") (pinfunction "2_2") (pintype "passive"))
    )
    (net (code "86") (name "Net-(D11-A)") (class "Default")
      (node (ref "D11") (pin "1") (pinfunction "A_1") (pintype "passive"))
      (node (ref "R11") (pin "2") (pinfunction "2_2") (pintype "passive"))
    )
    (net (code "87") (name "Net-(D12-A)") (class "Default")
      (node (ref "D12") (pin "1") (pinfunction "A_1") (pintype "passive"))
      (node (ref "R12") (pin "2") (pinfunction "2_2") (pintype "passive"))
    )
    (net (code "88") (name "Net-(D13-A)") (class "Default")
      (node (ref "D13") (pin "1") (pinfunction "A_1") (pintype "passive"))
      (node (ref "R13") (pin "2") (pinfunction "2_2") (pintype "passive"))
    )
    (net (code "89") (name "Net-(D14-A)") (class "Default")
      (node (ref "D14") (pin "1") (pinfunction "A_1") (pintype "passive"))
      (node (ref "R14") (pin "2") (pinfunction "2_2") (pintype "passive"))
    )
    (net (code "90") (name "Net-(D15-A)") (class "Default")
      (node (ref "D15") (pin "1") (pinfunction "A_1") (pintype "passive"))
      (node (ref "R15") (pin "2") (pinfunction "2_2") (pintype "passive"))
    )
    (net (code "91") (name "Net-(D16-A)") (class "Default")
      (node (ref "D16") (pin "1") (pinfunction "A_1") (pintype "passive"))
      (node (ref "R16") (pin "2") (pinfunction "2_2") (pintype "passive"))
    )
    (net (code "92") (name "Net-(LED17-A)") (class "Default")
      (node (ref "LED17") (pin "1") (pinfunction "A_1") (pintype "passive"))
      (node (ref "R17") (pin "2") (pinfunction "2_2") (pintype "passive"))
    )
    (net (code "93") (name "Net-(U1-Q7S)") (class "Default")
      (node (ref "U1") (pin "9") (pinfunction "Q7S_9") (pintype "passive"))
      (node (ref "U3") (pin "14") (pinfunction "DS_14") (pintype "passive"))
    )
    (net (code "94") (name "Net-(U5-C1+)") (class "Default")
      (node (ref "C4") (pin "2") (pinfunction "2_2") (pintype "passive"))
      (node (ref "U5") (pin "1") (pinfunction "C1+_1") (pintype "passive"))
    )
    (net (code "95") (name "Net-(U5-C1-)") (class "Default")
      (node (ref "C4") (pin "1") (pinfunction "1_1") (pintype "passive"))
      (node (ref "U5") (pin "3") (pinfunction "C1-_3") (pintype "passive"))
    )
    (net (code "96") (name "Net-(U5-C2+)") (class "Default")
      (node (ref "C5") (pin "2") (pinfunction "2_2") (pintype "passive"))
      (node (ref "U5") (pin "4") (pinfunction "C2+_4") (pintype "passive"))
    )
    (net (code "97") (name "Net-(U5-C2-)") (class "Default")
      (node (ref "C5") (pin "1") (pinfunction "1_1") (pintype "passive"))
      (node (ref "U5") (pin "5") (pinfunction "C2-_5") (pintype "passive"))
    )
    (net (code "98") (name "Net-(U5-V+)") (class "Default")
      (node (ref "C7") (pin "1") (pinfunction "1_1") (pintype "passive"))
      (node (ref "U5") (pin "2") (pinfunction "V+_2") (pintype "passive"))
    )
    (net (code "99") (name "Net-(U5-V-)") (class "Default")
      (node (ref "C8") (pin "1") (pinfunction "1_1") (pintype "passive"))
      (node (ref "U5") (pin "6") (pinfunction "V-_6") (pintype "passive"))
    )
    (net (code "100") (name "VCC") (class "Default")
      (node (ref "C2") (pin "2") (pinfunction "2_2") (pintype "passive"))
      (node (ref "C3") (pin "2") (pinfunction "2_2") (pintype "passive"))
      (node (ref "C6") (pin "1") (pinfunction "1_1") (pintype "passive"))
      (node (ref "J2") (pin "4") (pinfunction "+5V_4") (pintype "passive"))
      (node (ref "J4") (pin "20") (pinfunction "5V_20") (pintype "passive"))
      (node (ref "K1") (pin "1") (pinfunction "1_1") (pintype "passive"))
      (node (ref "K10") (pin "1") (pinfunction "1_1") (pintype "passive"))
      (node (ref "K11") (pin "1") (pinfunction "1_1") (pintype "passive"))
      (node (ref "K12") (pin "1") (pinfunction "1_1") (pintype "passive"))
      (node (ref "K13") (pin "1") (pinfunction "1_1") (pintype "passive"))
      (node (ref "K14") (pin "1") (pinfunction "1_1") (pintype "passive"))
      (node (ref "K15") (pin "1") (pinfunction "1_1") (pintype "passive"))
      (node (ref "K16") (pin "1") (pinfunction "1_1") (pintype "passive"))
      (node (ref "K2") (pin "1") (pinfunction "1_1") (pintype "passive"))
      (node (ref "K3") (pin "1") (pinfunction "1_1") (pintype "passive"))
      (node (ref "K4") (pin "1") (pinfunction "1_1") (pintype "passive"))
      (node (ref "K5") (pin "1") (pinfunction "1_1") (pintype "passive"))
      (node (ref "K6") (pin "1") (pinfunction "1_1") (pintype "passive"))
      (node (ref "K7") (pin "1") (pinfunction "1_1") (pintype "passive"))
      (node (ref "K8") (pin "1") (pinfunction "1_1") (pintype "passive"))
      (node (ref "K9") (pin "1") (pinfunction "1_1") (pintype "passive"))
      (node (ref "R1") (pin "1") (pinfunction "1_1") (pintype "passive"))
      (node (ref "R10") (pin "1") (pinfunction "1_1") (pintype "passive"))
      (node (ref "R11") (pin "1") (pinfunction "1_1") (pintype "passive"))
      (node (ref "R12") (pin "1") (pinfunction "1_1") (pintype "passive"))
      (node (ref "R13") (pin "1") (pinfunction "1_1") (pintype "passive"))
      (node (ref "R14") (pin "1") (pinfunction "1_1") (pintype "passive"))
      (node (ref "R15") (pin "1") (pinfunction "1_1") (pintype "passive"))
      (node (ref "R16") (pin "1") (pinfunction "1_1") (pintype "passive"))
      (node (ref "R2") (pin "1") (pinfunction "1_1") (pintype "passive"))
      (node (ref "R3") (pin "1") (pinfunction "1_1") (pintype "passive"))
      (node (ref "R4") (pin "1") (pinfunction "1_1") (pintype "passive"))
      (node (ref "R5") (pin "1") (pinfunction "1_1") (pintype "passive"))
      (node (ref "R6") (pin "1") (pinfunction "1_1") (pintype "passive"))
      (node (ref "R7") (pin "1") (pinfunction "1_1") (pintype "passive"))
      (node (ref "R8") (pin "1") (pinfunction "1_1") (pintype "passive"))
      (node (ref "R9") (pin "1") (pinfunction "1_1") (pintype "passive"))
      (node (ref "U1") (pin "10") (pinfunction "~{MR}_10") (pintype "passive"))
      (node (ref "U1") (pin "16") (pinfunction "Vcc_16") (pintype "passive"))
      (node (ref "U3") (pin "10") (pinfunction "~{MR}_10") (pintype "passive"))
      (node (ref "U3") (pin "16") (pinfunction "Vcc_16") (pintype "passive"))
      (node (ref "U5") (pin "16") (pinfunction "VCC_16") (pintype "passive"))
    )
    (net (code "101") (name "unconnected-(J1-D2-Pad5)") (class "Default")
      (node (ref "J1") (pin "5") (pinfunction "D2_5") (pintype "passive+no_connect"))
    )
    (net (code "102") (name "unconnected-(J1-RESET-Pad3)") (class "Default")
      (node (ref "J1") (pin "3") (pinfunction "RESET_3") (pintype "passive+no_connect"))
    )
    (net (code "103") (name "unconnected-(J2-A4-Pad8)") (class "Default")
      (node (ref "J2") (pin "8") (pinfunction "A4_8") (pintype "passive+no_connect"))
    )
    (net (code "104") (name "unconnected-(J2-A5-Pad7)") (class "Default")
      (node (ref "J2") (pin "7") (pinfunction "A5_7") (pintype "passive+no_connect"))
    )
    (net (code "105") (name "unconnected-(J2-A6-Pad6)") (class "Default")
      (node (ref "J2") (pin "6") (pinfunction "A6_6") (pintype "passive+no_connect"))
    )
    (net (code "106") (name "unconnected-(J2-A7-Pad5)") (class "Default")
      (node (ref "J2") (pin "5") (pinfunction "A7_5") (pintype "passive+no_connect"))
    )
    (net (code "107") (name "unconnected-(J2-RESET-Pad3)") (class "Default")
      (node (ref "J2") (pin "3") (pinfunction "RESET_3") (pintype "passive+no_connect"))
    )
    (net (code "108") (name "unconnected-(U2-CFDS-Pad10)") (class "Default")
      (node (ref "U2") (pin "10") (pinfunction "CFDS_10") (pintype "passive+no_connect"))
    )
    (net (code "109") (name "unconnected-(U3-Q7S-Pad9)") (class "Default")
      (node (ref "U3") (pin "9") (pinfunction "Q7S_9") (pintype "passive+no_connect"))
    )
    (net (code "110") (name "unconnected-(U4-CFDS-Pad10)") (class "Default")
      (node (ref "U4") (pin "10") (pinfunction "CFDS_10") (pintype "passive+no_connect"))
    )
    (net (code "111") (name "unconnected-(U5-R2IN-Pad8)") (class "Default")
      (node (ref "U5") (pin "8") (pinfunction "R2IN_8") (pintype "passive+no_connect"))
    )
    (net (code "112") (name "unconnected-(U5-R2OUT-Pad9)") (class "Default")
      (node (ref "U5") (pin "9") (pinfunction "R2OUT_9") (pintype "passive+no_connect"))
    )
    (net (code "113") (name "unconnected-(U5-T2IN-Pad10)") (class "Default")
      (node (ref "U5") (pin "10") (pinfunction "T2IN_10") (pintype "passive+no_connect"))
    )
    (net (code "114") (name "unconnected-(U5-T2OUT-Pad7)") (class "Default")
      (node (ref "U5") (pin "7") (pinfunction "T2OUT_7") (pintype "passive+no_connect"))
    )
  )
)
